# Voeding.net
KiCad netlist of a schematic drawn in Altium Designer
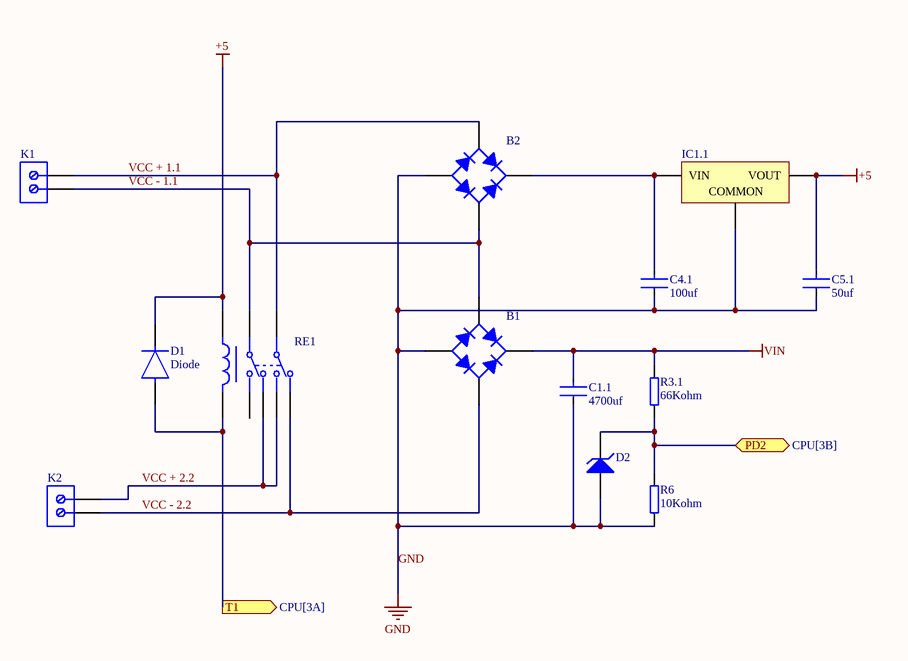
[diagram p0: Voeding.SchDoc]

(export (version "E")
  (design (tool "Eeschema 10.0.6"))
  (components
    (comp (ref "B1")
      (value "Bridge_Rectifier")
      (footprint "ttf")
      (fields (field (name "MANUFACTURER") "Diodes Inc"))
      (libsource (lib "Soldeerstation_Final") (part "Bridge_Rectifier"))
    )
    (comp (ref "B2")
      (value "Bridge_Rectifier")
      (footprint "ttf")
      (fields (field (name "MANUFACTURER") "Diodes Inc"))
      (libsource (lib "Soldeerstation_Final") (part "Bridge_Rectifier"))
    )
    (comp (ref "C1.1")
      (value "4700uf")
      (footprint "CE_D25_L25_plugin")
      (fields
        (field (name "MANUFACTURER") "KEMET")
        (field (name "OCTOPART") "https://octopart.com/c0805c224k5ractu-kemet-144670")
        (field (name "MANUFACTURER PART NUMBER") "C0805C224K5RACTU")
      )
      (libsource (lib "Soldeerstation_Final") (part "Capacitor_Ceramic"))
    )
    (comp (ref "C4.1")
      (value "100uf")
      (footprint "CC_0805_L")
      (fields
        (field (name "MANUFACTURER") "KEMET")
        (field (name "OCTOPART") "https://octopart.com/c0805c224k5ractu-kemet-144670")
        (field (name "MANUFACTURER PART NUMBER") "C0805C224K5RACTU")
      )
      (libsource (lib "Soldeerstation_Final") (part "Capacitor_Ceramic"))
    )
    (comp (ref "C5.1")
      (value "50uf")
      (footprint "CC_0805_L")
      (fields
        (field (name "MANUFACTURER") "KEMET")
        (field (name "OCTOPART") "https://octopart.com/c0805c224k5ractu-kemet-144670")
        (field (name "MANUFACTURER PART NUMBER") "C0805C224K5RACTU")
      )
      (libsource (lib "Soldeerstation_Final") (part "Capacitor_Ceramic"))
    )
    (comp (ref "D1")
      (value "Diode")
      (footprint "SOD-123FL")
      (fields
        (field (name "MANUFACTURER PART NUMBER") "1N4007")
        (field (name "MANUFACTURER") "Diotec")
        (field (name "OCTOPART") "https://octopart.com/1n4007-diotec-4040411")
      )
      (libsource (lib "Soldeerstation_Final") (part "Diode"))
    )
    (comp (ref "D2")
      (value "Zener_Diode")
      (footprint "SOD-123FL")
      (fields (field (name "MANUFACTURER") "On Semiconductor") (field (name "PARTNUMBER") "1SMB5920BT3G"))
      (libsource (lib "Soldeerstation_Final") (part "Zener_Diode"))
    )
    (comp (ref "IC1.1")
      (value "OKI-78SR-5/1.5-W36-C")
      (footprint "OKI78SR515W36C")
      (description "Non-Isolated DC/DC Converter, 7.5 W, 7 to 36 V, 1.5 A, -40 to 85 degC, 3-Pin THD, RoHS")
      (fields (field (name "MANUFACTURER") "Murata"))
      (libsource (lib "Soldeerstation_Final") (part "OKI-78SR-5/1.5-W36-C"))
    )
    (comp (ref "K1")
      (value "282836-2")
      (footprint "terminal_block")
      (description "Female Header, Pitch 5 mm, 1 x 2 Position, Height 10 mm, Tail Length 3.5 mm, Rohs, Bulk")
      (fields (field (name "VOLTAGE") "300V") (field (name "MANUFACTURER") "TE Connectivity"))
      (libsource (lib "Schlib1") (part "1x2 terminal block"))
    )
    (comp (ref "K2")
      (value "282836-2")
      (footprint "terminal_block")
      (description "Female Header, Pitch 5 mm, 1 x 2 Position, Height 10 mm, Tail Length 3.5 mm, Rohs, Bulk")
      (fields (field (name "VOLTAGE") "300V") (field (name "MANUFACTURER") "TE Connectivity"))
      (libsource (lib "Schlib1") (part "1x2 terminal block"))
    )
    (comp (ref "R3.1")
      (value "66Kohm")
      (footprint "CC_0805_m")
      (fields (field (name "MANUFACTURER") "Vishay Dale") (field (name "PART NUMBER") "CRCW08050000Z0EA"))
      (libsource (lib "Soldeerstation_Final") (part "Resistor"))
    )
    (comp (ref "R6")
      (value "10Kohm")
      (footprint "CC_0805_m")
      (fields (field (name "MANUFACTURER") "Vishay Dale") (field (name "PART NUMBER") "CRCW08050000Z0EA"))
      (libsource (lib "Soldeerstation_Final") (part "Resistor"))
    )
    (comp (ref "RE1")
      (value "RELAY_GENERAL_PURPOSE")
      (footprint "RT42")
      (fields
        (field (name "MANUFACTURER PART NUMBER") "RT424005")
        (field (name "OCTOPART") "https://octopart.com/5-1393243-9-te+connectivity-41835766")
        (field (name "MANUFACTURER") "TE Connectivity")
      )
      (libsource (lib "Soldeerstation_Final") (part "RELAY_GENERAL_PURPOSE"))
    )
  )
  (nets
    (net (code "1") (name "+5") (class "Default")
      (node (ref "C5.1") (pin "1") (pinfunction "1_1") (pintype "passive"))
      (node (ref "D1") (pin "1") (pinfunction "C_1") (pintype "passive"))
      (node (ref "IC1.1") (pin "3") (pinfunction "VOUT_3") (pintype "power_in"))
      (node (ref "RE1") (pin "A1") (pinfunction "A1_A1") (pintype "passive"))
    )
    (net (code "2") (name "/PD2") (class "Default")
      (node (ref "D2") (pin "1") (pinfunction "K_1") (pintype "passive"))
      (node (ref "R3.1") (pin "2") (pinfunction "2_2") (pintype "passive"))
      (node (ref "R6") (pin "1") (pinfunction "1_1") (pintype "passive"))
    )
    (net (code "3") (name "/T1") (class "Default")
      (node (ref "D1") (pin "2") (pinfunction "A_2") (pintype "passive"))
      (node (ref "RE1") (pin "A2") (pinfunction "A2_A2") (pintype "passive"))
    )
    (net (code "4") (name "/VCC + 1.1") (class "Default")
      (node (ref "B2") (pin "3") (pinfunction "C_3") (pintype "passive"))
      (node (ref "K1") (pin "2") (pinfunction "2_2") (pintype "passive"))
      (node (ref "RE1") (pin "21") (pinfunction "21_21") (pintype "passive"))
    )
    (net (code "5") (name "/VCC + 2.2") (class "Default")
      (node (ref "K2") (pin "2") (pinfunction "2_2") (pintype "passive"))
      (node (ref "RE1") (pin "12") (pinfunction "12_12") (pintype "passive"))
      (node (ref "RE1") (pin "24") (pinfunction "24_24") (pintype "passive"))
    )
    (net (code "6") (name "/VCC - 1.1") (class "Default")
      (node (ref "B1") (pin "3") (pinfunction "C_3") (pintype "passive"))
      (node (ref "B2") (pin "4") (pinfunction "C_4") (pintype "passive"))
      (node (ref "K1") (pin "1") (pinfunction "1_1") (pintype "passive"))
      (node (ref "RE1") (pin "11") (pinfunction "11_11") (pintype "passive"))
    )
    (net (code "7") (name "/VCC - 2.2") (class "Default")
      (node (ref "B1") (pin "4") (pinfunction "C_4") (pintype "passive"))
      (node (ref "K2") (pin "1") (pinfunction "1_1") (pintype "passive"))
      (node (ref "RE1") (pin "22") (pinfunction "22_22") (pintype "passive"))
    )
    (net (code "8") (name "GND") (class "Default")
      (node (ref "B1") (pin "2") (pinfunction "A_2") (pintype "passive"))
      (node (ref "B2") (pin "2") (pinfunction "A_2") (pintype "passive"))
      (node (ref "C1.1") (pin "2") (pinfunction "2_2") (pintype "passive"))
      (node (ref "C4.1") (pin "2") (pinfunction "2_2") (pintype "passive"))
      (node (ref "C5.1") (pin "2") (pinfunction "2_2") (pintype "passive"))
      (node (ref "D2") (pin "2") (pinfunction "A_2") (pintype "passive"))
      (node (ref "IC1.1") (pin "2") (pinfunction "COMMON_2") (pintype "power_in"))
      (node (ref "R6") (pin "2") (pinfunction "2_2") (pintype "passive"))
    )
    (net (code "9") (name "Net-(B2-K)") (class "Default")
      (node (ref "B2") (pin "1") (pinfunction "K_1") (pintype "passive"))
      (node (ref "C4.1") (pin "1") (pinfunction "1_1") (pintype "passive"))
      (node (ref "IC1.1") (pin "1") (pinfunction "VIN_1") (pintype "power_in"))
    )
    (net (code "10") (name "VIN") (class "Default")
      (node (ref "B1") (pin "1") (pinfunction "K_1") (pintype "passive"))
      (node (ref "C1.1") (pin "1") (pinfunction "1_1") (pintype "passive"))
      (node (ref "R3.1") (pin "1") (pinfunction "1_1") (pintype "passive"))
    )
    (net (code "11") (name "unconnected-(RE1-Pad14)") (class "Default")
      (node (ref "RE1") (pin "14") (pinfunction "14_14") (pintype "passive"))
    )
  )
)
